# Watch_timer.net
KiCad netlist of a schematic drawn in EAGLE
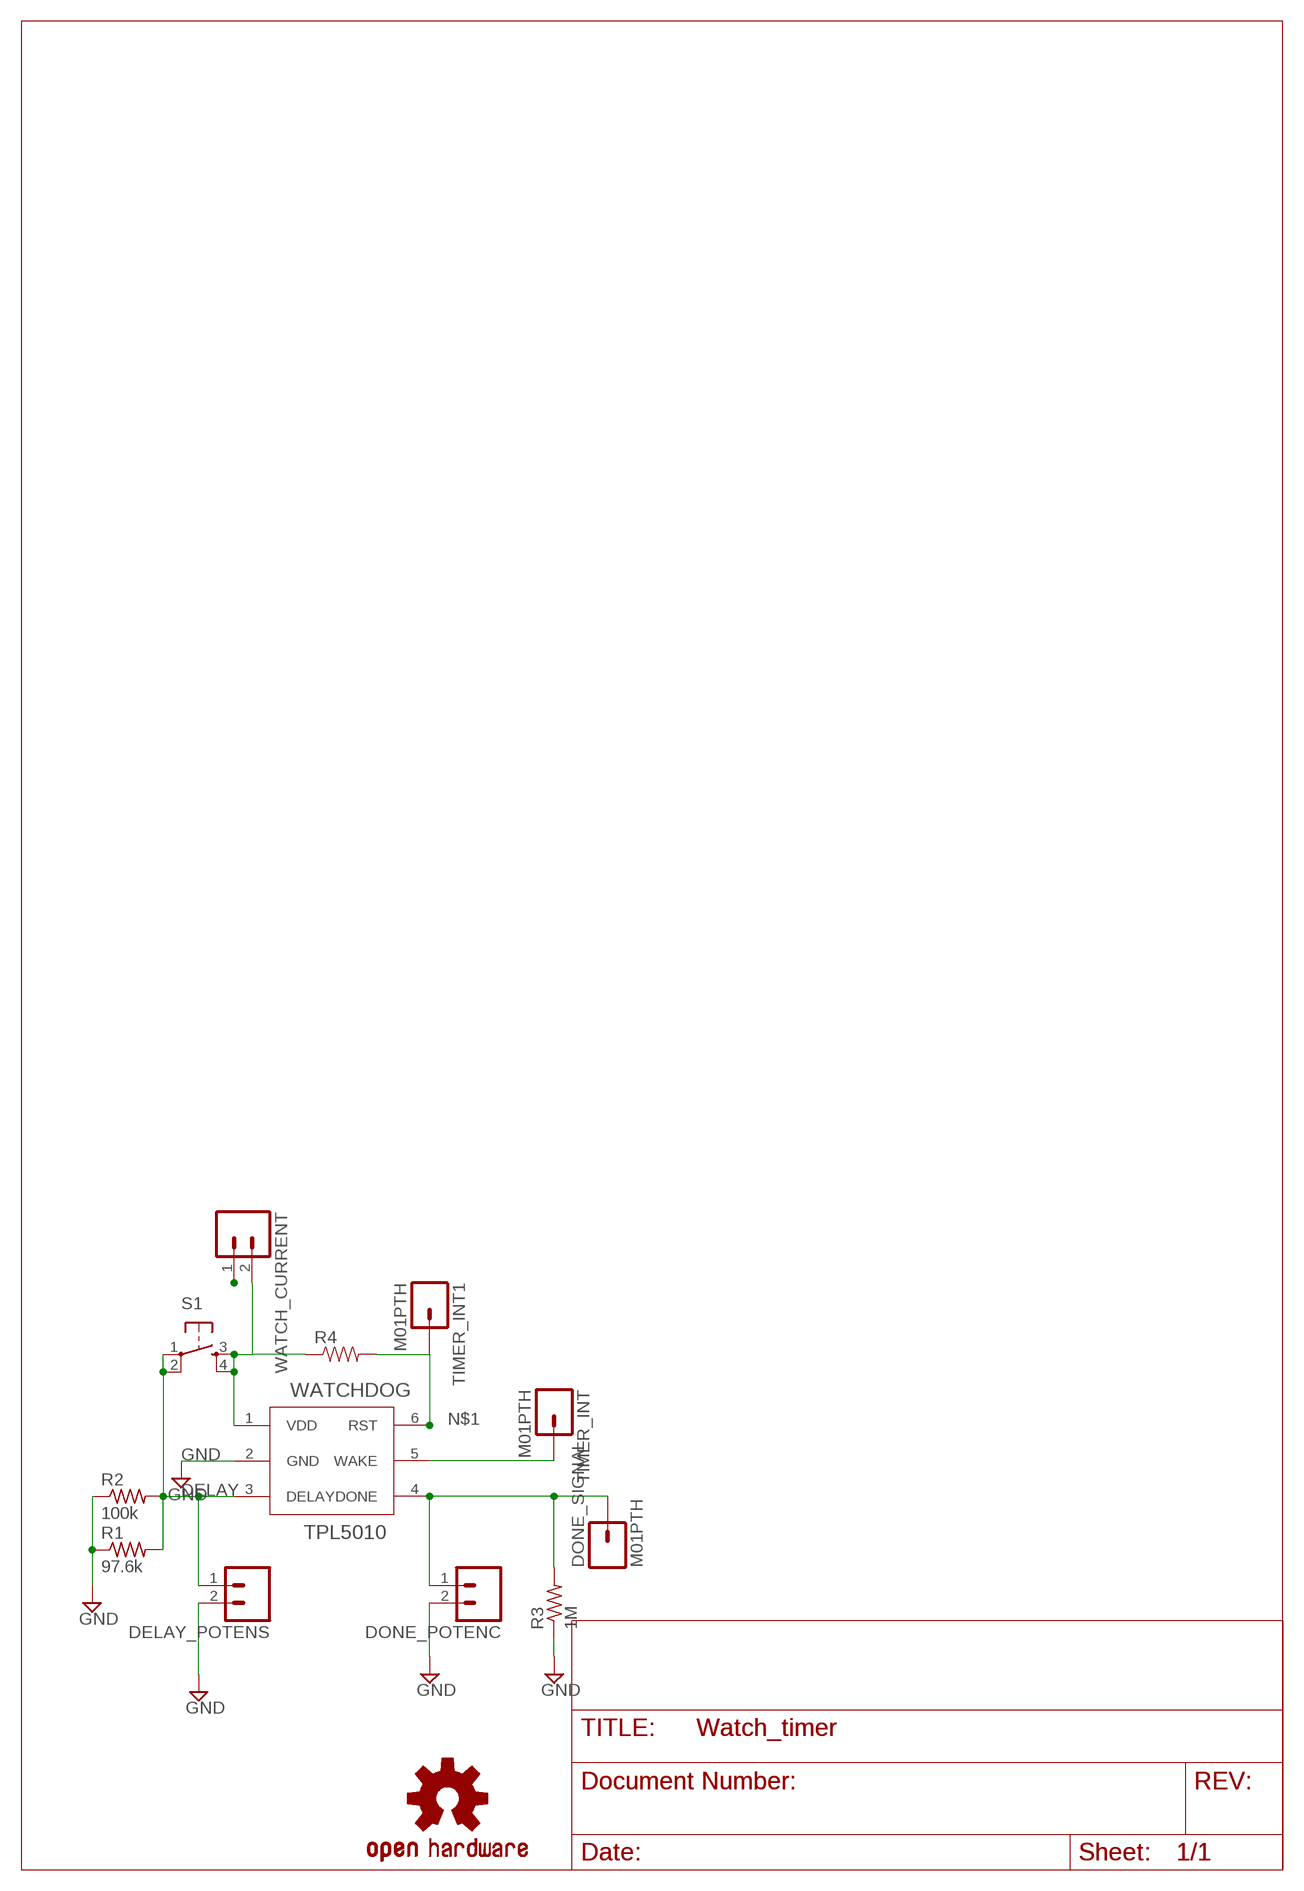
[diagram p0: schematic, sheet 1]

(export (version "E")
  (design (tool "Eeschema 10.0.6"))
  (components
    (comp (ref "DELAY_POTENS")
      (value "M02PTH")
      (footprint "eagle-import:1X02")
      (libsource (lib "eagle-import") (part "M02PTH"))
    )
    (comp (ref "DONE_POTENC")
      (value "M02PTH")
      (footprint "eagle-import:1X02")
      (libsource (lib "eagle-import") (part "M02PTH"))
    )
    (comp (ref "DONE_SIGNAL")
      (value "M01PTH")
      (footprint "eagle-import:1X01")
      (libsource (lib "eagle-import") (part "M01PTH"))
    )
    (comp (ref "LOGO1")
      (value "OSHW-LOGOL")
      (footprint "eagle-import:OSHW-LOGO-L")
      (libsource (lib "eagle-import") (part "OSHW-LOGOL"))
    )
    (comp (ref "R1")
      (value "97.6k")
      (footprint "eagle-import:R0805")
      (libsource (lib "eagle-import") (part "R-US_R0805"))
    )
    (comp (ref "R2")
      (value "100k")
      (footprint "eagle-import:R0805")
      (libsource (lib "eagle-import") (part "R-US_R0805"))
    )
    (comp (ref "R3")
      (value "1M")
      (footprint "eagle-import:R0805")
      (libsource (lib "eagle-import") (part "R-US_R0805"))
    )
    (comp (ref "R4")
      (value "RESISTOR0603-RES")
      (footprint "eagle-import:0603-RES")
      (libsource (lib "eagle-import") (part "RESISTOR0603-RES"))
    )
    (comp (ref "S1")
      (value "TAC_SWITCHSMD")
      (footprint "eagle-import:TACTILE_SWITCH_SMD")
      (libsource (lib "eagle-import") (part "TAC_SWITCHSMD"))
    )
    (comp (ref "TIMER_INT")
      (value "M01PTH")
      (footprint "eagle-import:1X01")
      (libsource (lib "eagle-import") (part "M01PTH"))
    )
    (comp (ref "TIMER_INT1")
      (value "M01PTH")
      (footprint "eagle-import:1X01")
      (libsource (lib "eagle-import") (part "M01PTH"))
    )
    (comp (ref "WATCHDOG")
      (value "TPL5010")
      (footprint "eagle-import:TSOT-23")
      (libsource (lib "eagle-import") (part "TPL5010"))
    )
    (comp (ref "WATCH_CURRENT")
      (value "M02PTH")
      (footprint "eagle-import:1X02")
      (libsource (lib "eagle-import") (part "M02PTH"))
    )
  )
  (nets
    (net (code "1") (name "/DELAY") (class "Default")
      (node (ref "DELAY_POTENS") (pin "1") (pinfunction "1_1") (pintype "passive"))
      (node (ref "R1") (pin "2") (pinfunction "2_2") (pintype "passive"))
      (node (ref "R2") (pin "2") (pinfunction "2_2") (pintype "passive"))
      (node (ref "S1") (pin "1") (pinfunction "1_1") (pintype "passive"))
      (node (ref "S1") (pin "2") (pinfunction "2_2") (pintype "passive"))
      (node (ref "WATCHDOG") (pin "3") (pinfunction "DELAY_3") (pintype "power_in"))
    )
    (net (code "2") (name "/N$1") (class "Default")
      (node (ref "R4") (pin "2") (pinfunction "2_2") (pintype "passive"))
      (node (ref "TIMER_INT1") (pin "1") (pinfunction "1_1") (pintype "passive"))
      (node (ref "WATCHDOG") (pin "6") (pinfunction "RST_6") (pintype "power_in"))
    )
    (net (code "3") (name "GND") (class "Default")
      (node (ref "DELAY_POTENS") (pin "2") (pinfunction "2_2") (pintype "passive"))
      (node (ref "DONE_POTENC") (pin "2") (pinfunction "2_2") (pintype "passive"))
      (node (ref "R1") (pin "1") (pinfunction "1_1") (pintype "passive"))
      (node (ref "R2") (pin "1") (pinfunction "1_1") (pintype "passive"))
      (node (ref "R3") (pin "1") (pinfunction "1_1") (pintype "passive"))
      (node (ref "WATCHDOG") (pin "2") (pinfunction "GND_2") (pintype "input"))
    )
    (net (code "4") (name "Net-(WATCHDOG-DONE)") (class "Default")
      (node (ref "DONE_POTENC") (pin "1") (pinfunction "1_1") (pintype "passive"))
      (node (ref "DONE_SIGNAL") (pin "1") (pinfunction "1_1") (pintype "passive"))
      (node (ref "R3") (pin "2") (pinfunction "2_2") (pintype "passive"))
      (node (ref "WATCHDOG") (pin "4") (pinfunction "DONE_4") (pintype "input"))
    )
    (net (code "5") (name "Net-(WATCHDOG-VDD)") (class "Default")
      (node (ref "R4") (pin "1") (pinfunction "1_1") (pintype "passive"))
      (node (ref "S1") (pin "3") (pinfunction "3_3") (pintype "passive"))
      (node (ref "S1") (pin "4") (pinfunction "4_4") (pintype "passive"))
      (node (ref "WATCHDOG") (pin "1") (pinfunction "VDD_1") (pintype "power_in"))
      (node (ref "WATCH_CURRENT") (pin "2") (pinfunction "2_2") (pintype "passive"))
    )
    (net (code "6") (name "Net-(WATCHDOG-WAKE)") (class "Default")
      (node (ref "TIMER_INT") (pin "1") (pinfunction "1_1") (pintype "passive"))
      (node (ref "WATCHDOG") (pin "5") (pinfunction "WAKE_5") (pintype "bidirectional"))
    )
    (net (code "7") (name "unconnected-(WATCH_CURRENT-Pad1)") (class "Default")
      (node (ref "WATCH_CURRENT") (pin "1") (pinfunction "1_1") (pintype "passive"))
    )
  )
)
